# EAGLESSTC2.net
KiCad netlist of a schematic drawn in EAGLE
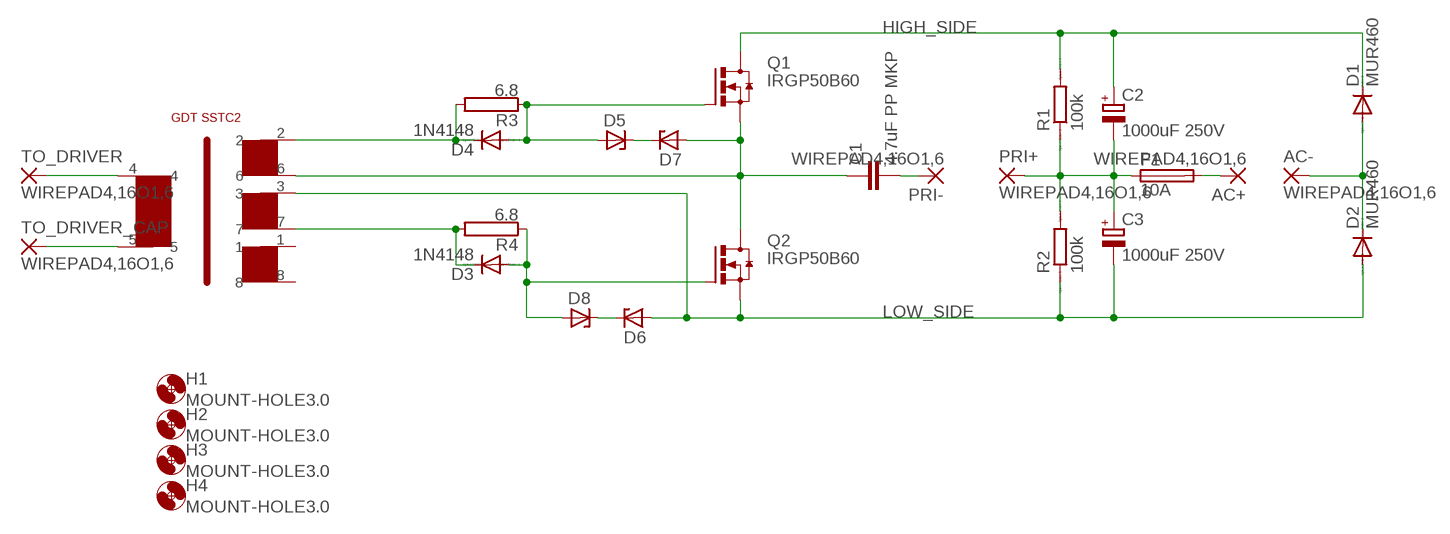
[diagram p0: schematic, sheet 1]

(export (version "E")
  (design (tool "Eeschema 10.0.6"))
  (components
    (comp (ref "AC+")
      (value "WIREPAD4,16O1,6")
      (footprint "eagle-import:4,16O1,6")
      (libsource (lib "eagle-import") (part "WIREPAD4,16O1,6"))
    )
    (comp (ref "AC-")
      (value "WIREPAD4,16O1,6")
      (footprint "eagle-import:4,16O1,6")
      (libsource (lib "eagle-import") (part "WIREPAD4,16O1,6"))
    )
    (comp (ref "C1")
      (value "4.7uF PP MKP")
      (footprint "eagle-import:C37.5B20")
      (libsource (lib "eagle-import") (part "C37/20"))
    )
    (comp (ref "C2")
      (value "1000uF 250V")
      (footprint "eagle-import:EB35D")
      (libsource (lib "eagle-import") (part "CPOL-EUE10-35"))
    )
    (comp (ref "C3")
      (value "1000uF 250V")
      (footprint "eagle-import:EB35D")
      (libsource (lib "eagle-import") (part "CPOL-EUE10-35"))
    )
    (comp (ref "D1")
      (value "MUR460")
      (footprint "eagle-import:C2673")
      (libsource (lib "eagle-import") (part "MUR440RL"))
    )
    (comp (ref "D2")
      (value "MUR460")
      (footprint "eagle-import:C2673")
      (libsource (lib "eagle-import") (part "MUR440RL"))
    )
    (comp (ref "D3")
      (value "1N4148")
      (footprint "eagle-import:DO35-10")
      (libsource (lib "eagle-import") (part "1N4148DO35-10"))
    )
    (comp (ref "D4")
      (value "1N4148")
      (footprint "eagle-import:DO35-10")
      (libsource (lib "eagle-import") (part "1N4148DO35-10"))
    )
    (comp (ref "D5")
      (value "ZENER-DIODEZD-10")
      (footprint "eagle-import:ZDIO-10")
      (libsource (lib "eagle-import") (part "ZENER-DIODEZD-10"))
    )
    (comp (ref "D6")
      (value "ZENER-DIODEZD-10")
      (footprint "eagle-import:ZDIO-10")
      (libsource (lib "eagle-import") (part "ZENER-DIODEZD-10"))
    )
    (comp (ref "D7")
      (value "ZENER-DIODEZD-10")
      (footprint "eagle-import:ZDIO-10")
      (libsource (lib "eagle-import") (part "ZENER-DIODEZD-10"))
    )
    (comp (ref "D8")
      (value "ZENER-DIODEZD-10")
      (footprint "eagle-import:ZDIO-10")
      (libsource (lib "eagle-import") (part "ZENER-DIODEZD-10"))
    )
    (comp (ref "F1")
      (value "10A")
      (footprint "eagle-import:SH22")
      (libsource (lib "eagle-import") (part "FUSESH22"))
    )
    (comp (ref "H1")
      (value "MOUNT-HOLE3.0")
      (footprint "eagle-import:3,0")
      (libsource (lib "eagle-import") (part "MOUNT-HOLE3.0"))
    )
    (comp (ref "H2")
      (value "MOUNT-HOLE3.0")
      (footprint "eagle-import:3,0")
      (libsource (lib "eagle-import") (part "MOUNT-HOLE3.0"))
    )
    (comp (ref "H3")
      (value "MOUNT-HOLE3.0")
      (footprint "eagle-import:3,0")
      (libsource (lib "eagle-import") (part "MOUNT-HOLE3.0"))
    )
    (comp (ref "H4")
      (value "MOUNT-HOLE3.0")
      (footprint "eagle-import:3,0")
      (libsource (lib "eagle-import") (part "MOUNT-HOLE3.0"))
    )
    (comp (ref "PRI+")
      (value "WIREPAD4,16O1,6")
      (footprint "eagle-import:4,16O1,6")
      (libsource (lib "eagle-import") (part "WIREPAD4,16O1,6"))
    )
    (comp (ref "PRI-")
      (value "WIREPAD4,16O1,6")
      (footprint "eagle-import:4,16O1,6")
      (libsource (lib "eagle-import") (part "WIREPAD4,16O1,6"))
    )
    (comp (ref "Q1")
      (value "IRGP50B60")
      (footprint "eagle-import:TO-247AD-V")
      (libsource (lib "eagle-import") (part "IRFP250"))
    )
    (comp (ref "Q2")
      (value "IRGP50B60")
      (footprint "eagle-import:TO-247AD-V")
      (libsource (lib "eagle-import") (part "IRFP250"))
    )
    (comp (ref "R1")
      (value "100k")
      (footprint "eagle-import:0207_10")
      (libsource (lib "eagle-import") (part "R0207/10"))
    )
    (comp (ref "R2")
      (value "100k")
      (footprint "eagle-import:0207_10")
      (libsource (lib "eagle-import") (part "R0207/10"))
    )
    (comp (ref "R3")
      (value "6.8")
      (footprint "eagle-import:RWM6X22")
      (libsource (lib "eagle-import") (part "RRWM6X22"))
    )
    (comp (ref "R4")
      (value "6.8")
      (footprint "eagle-import:RWM6X22")
      (libsource (lib "eagle-import") (part "RRWM6X22"))
    )
    (comp (ref "TO_DRIVER")
      (value "WIREPAD4,16O1,6")
      (footprint "eagle-import:4,16O1,6")
      (libsource (lib "eagle-import") (part "WIREPAD4,16O1,6"))
    )
    (comp (ref "TO_DRIVER_CAP")
      (value "WIREPAD4,16O1,6")
      (footprint "eagle-import:4,16O1,6")
      (libsource (lib "eagle-import") (part "WIREPAD4,16O1,6"))
    )
    (comp (ref "U$1")
      (value "ATX-TRANSFORMER_01")
      (footprint "eagle-import:ATX-TRANSFORMER_01")
      (libsource (lib "eagle-import") (part "ATX-TRANSFORMER_01"))
    )
  )
  (nets
    (net (code "1") (name "/HIGH_SIDE") (class "Default")
      (node (ref "C2") (pin "+") (pinfunction "+_+") (pintype "passive"))
      (node (ref "D1") (pin "C") (pinfunction "C_C") (pintype "passive"))
      (node (ref "Q1") (pin "D") (pinfunction "D_D") (pintype "passive"))
      (node (ref "R1") (pin "2") (pinfunction "2_2") (pintype "passive"))
    )
    (net (code "2") (name "/LOW_SIDE") (class "Default")
      (node (ref "C3") (pin "-") (pinfunction "-_-") (pintype "passive"))
      (node (ref "D2") (pin "A") (pinfunction "A_A") (pintype "passive"))
      (node (ref "D6") (pin "A") (pinfunction "A_A") (pintype "passive"))
      (node (ref "Q2") (pin "S") (pinfunction "S_S") (pintype "passive"))
      (node (ref "R2") (pin "1") (pinfunction "1_1") (pintype "passive"))
      (node (ref "U$1") (pin "3") (pinfunction "3_3") (pintype "bidirectional"))
    )
    (net (code "3") (name "Net-(AC+-P)") (class "Default")
      (node (ref "AC+") (pin "1") (pinfunction "P_1") (pintype "passive"))
      (node (ref "F1") (pin "2") (pinfunction "2_2") (pintype "passive"))
    )
    (net (code "4") (name "Net-(AC--P)") (class "Default")
      (node (ref "AC-") (pin "1") (pinfunction "P_1") (pintype "passive"))
      (node (ref "D1") (pin "A") (pinfunction "A_A") (pintype "passive"))
      (node (ref "D2") (pin "C") (pinfunction "C_C") (pintype "passive"))
    )
    (net (code "5") (name "Net-(C1-Pad1)") (class "Default")
      (node (ref "C1") (pin "1") (pinfunction "1_1") (pintype "passive"))
      (node (ref "D7") (pin "A") (pinfunction "A_A") (pintype "passive"))
      (node (ref "Q1") (pin "S") (pinfunction "S_S") (pintype "passive"))
      (node (ref "Q2") (pin "D") (pinfunction "D_D") (pintype "passive"))
      (node (ref "U$1") (pin "6") (pinfunction "6_6") (pintype "bidirectional"))
    )
    (net (code "6") (name "Net-(D3-PadA)") (class "Default")
      (node (ref "D3") (pin "A") (pinfunction "A_A") (pintype "passive"))
      (node (ref "D8") (pin "A") (pinfunction "A_A") (pintype "passive"))
      (node (ref "Q2") (pin "G") (pinfunction "G_G") (pintype "passive"))
      (node (ref "R4") (pin "1") (pinfunction "1_1") (pintype "passive"))
    )
    (net (code "7") (name "Net-(D3-PadC)") (class "Default")
      (node (ref "D3") (pin "C") (pinfunction "C_C") (pintype "passive"))
      (node (ref "R4") (pin "2") (pinfunction "2_2") (pintype "passive"))
      (node (ref "U$1") (pin "7") (pinfunction "7_7") (pintype "bidirectional"))
    )
    (net (code "8") (name "Net-(D4-PadA)") (class "Default")
      (node (ref "D4") (pin "A") (pinfunction "A_A") (pintype "passive"))
      (node (ref "D5") (pin "A") (pinfunction "A_A") (pintype "passive"))
      (node (ref "Q1") (pin "G") (pinfunction "G_G") (pintype "passive"))
      (node (ref "R3") (pin "1") (pinfunction "1_1") (pintype "passive"))
    )
    (net (code "9") (name "Net-(D4-PadC)") (class "Default")
      (node (ref "D4") (pin "C") (pinfunction "C_C") (pintype "passive"))
      (node (ref "R3") (pin "2") (pinfunction "2_2") (pintype "passive"))
      (node (ref "U$1") (pin "2") (pinfunction "2_2") (pintype "bidirectional"))
    )
    (net (code "10") (name "Net-(D5-PadC)") (class "Default")
      (node (ref "D5") (pin "C") (pinfunction "C_C") (pintype "passive"))
      (node (ref "D7") (pin "C") (pinfunction "C_C") (pintype "passive"))
    )
    (net (code "11") (name "Net-(D6-PadC)") (class "Default")
      (node (ref "D6") (pin "C") (pinfunction "C_C") (pintype "passive"))
      (node (ref "D8") (pin "C") (pinfunction "C_C") (pintype "passive"))
    )
    (net (code "12") (name "Net-(PRI+-P)") (class "Default")
      (node (ref "C2") (pin "-") (pinfunction "-_-") (pintype "passive"))
      (node (ref "C3") (pin "+") (pinfunction "+_+") (pintype "passive"))
      (node (ref "F1") (pin "1") (pinfunction "1_1") (pintype "passive"))
      (node (ref "PRI+") (pin "1") (pinfunction "P_1") (pintype "passive"))
      (node (ref "R1") (pin "1") (pinfunction "1_1") (pintype "passive"))
      (node (ref "R2") (pin "2") (pinfunction "2_2") (pintype "passive"))
    )
    (net (code "13") (name "Net-(PRI--P)") (class "Default")
      (node (ref "C1") (pin "2") (pinfunction "2_2") (pintype "passive"))
      (node (ref "PRI-") (pin "1") (pinfunction "P_1") (pintype "passive"))
    )
    (net (code "14") (name "Net-(TO_DRIVER-P)") (class "Default")
      (node (ref "TO_DRIVER") (pin "1") (pinfunction "P_1") (pintype "passive"))
      (node (ref "U$1") (pin "4") (pinfunction "4_4") (pintype "bidirectional"))
    )
    (net (code "15") (name "Net-(TO_DRIVER_CAP-P)") (class "Default")
      (node (ref "TO_DRIVER_CAP") (pin "1") (pinfunction "P_1") (pintype "passive"))
      (node (ref "U$1") (pin "5") (pinfunction "5_5") (pintype "bidirectional"))
    )
    (net (code "16") (name "unconnected-(U$1-Pad1)") (class "Default")
      (node (ref "U$1") (pin "1") (pinfunction "1_1") (pintype "bidirectional"))
    )
    (net (code "17") (name "unconnected-(U$1-Pad8)") (class "Default")
      (node (ref "U$1") (pin "8") (pinfunction "8_8") (pintype "bidirectional"))
    )
  )
)
